# NetworkArduino.net
KiCad netlist of a schematic drawn in EAGLE
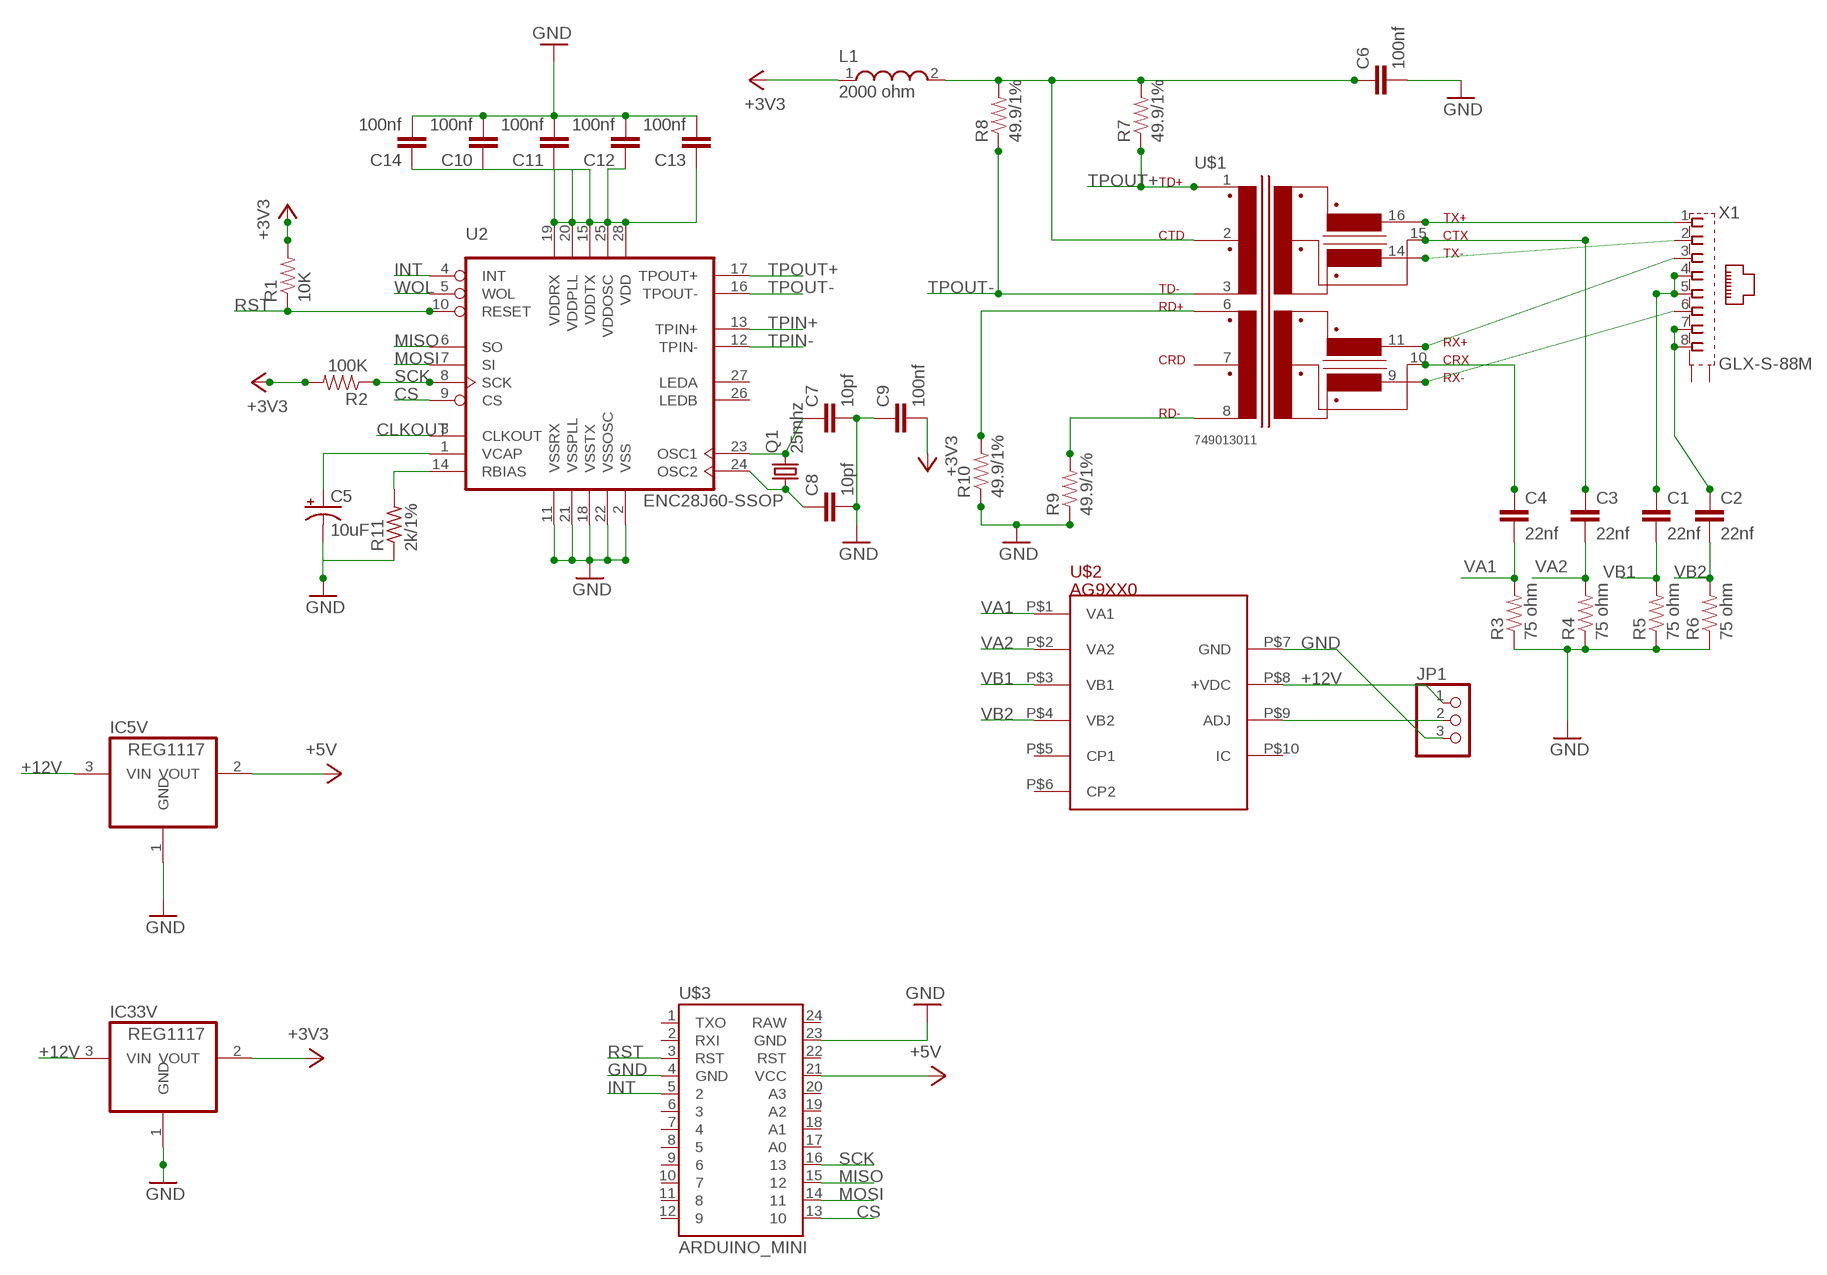
[diagram p0: schematic, sheet 1]

(export (version "E")
  (design (tool "Eeschema 10.0.6"))
  (components
    (comp (ref "C1")
      (value "22nf")
      (footprint "eagle-import:0805")
      (libsource (lib "eagle-import") (part "CAP0805"))
    )
    (comp (ref "C2")
      (value "22nf")
      (footprint "eagle-import:0805")
      (libsource (lib "eagle-import") (part "CAP0805"))
    )
    (comp (ref "C3")
      (value "22nf")
      (footprint "eagle-import:0805")
      (libsource (lib "eagle-import") (part "CAP0805"))
    )
    (comp (ref "C4")
      (value "22nf")
      (footprint "eagle-import:0805")
      (libsource (lib "eagle-import") (part "CAP0805"))
    )
    (comp (ref "C5")
      (value "10uF")
      (footprint "eagle-import:EIA3216")
      (libsource (lib "eagle-import") (part "10UF-16V-10%(TANT)"))
    )
    (comp (ref "C6")
      (value "100nf")
      (footprint "eagle-import:0805")
      (libsource (lib "eagle-import") (part "CAP0805"))
    )
    (comp (ref "C7")
      (value "10pf")
      (footprint "eagle-import:0805")
      (libsource (lib "eagle-import") (part "CAP0805"))
    )
    (comp (ref "C8")
      (value "10pf")
      (footprint "eagle-import:0805")
      (libsource (lib "eagle-import") (part "CAP0805"))
    )
    (comp (ref "C9")
      (value "100nf")
      (footprint "eagle-import:0805")
      (libsource (lib "eagle-import") (part "CAP0805"))
    )
    (comp (ref "C10")
      (value "100nf")
      (footprint "eagle-import:0805")
      (libsource (lib "eagle-import") (part "CAP0805"))
    )
    (comp (ref "C11")
      (value "100nf")
      (footprint "eagle-import:0805")
      (libsource (lib "eagle-import") (part "CAP0805"))
    )
    (comp (ref "C12")
      (value "100nf")
      (footprint "eagle-import:0805")
      (libsource (lib "eagle-import") (part "CAP0805"))
    )
    (comp (ref "C13")
      (value "100nf")
      (footprint "eagle-import:0805")
      (libsource (lib "eagle-import") (part "CAP0805"))
    )
    (comp (ref "C14")
      (value "100nf")
      (footprint "eagle-import:0805")
      (libsource (lib "eagle-import") (part "CAP0805"))
    )
    (comp (ref "IC5V")
      (value "REG1117")
      (footprint "eagle-import:SOT223")
      (libsource (lib "eagle-import") (part "REG1117"))
    )
    (comp (ref "IC33V")
      (value "REG1117")
      (footprint "eagle-import:SOT223")
      (libsource (lib "eagle-import") (part "REG1117"))
    )
    (comp (ref "JP1")
      (value "PINHD-1X3")
      (footprint "eagle-import:1X03")
      (libsource (lib "eagle-import") (part "PINHD-1X3"))
    )
    (comp (ref "L1")
      (value "2000 ohm")
      (footprint "eagle-import:WE-CBA_0805(W=3)")
      (libsource (lib "eagle-import") (part "WE-CBA_0805(WB/HS)"))
    )
    (comp (ref "Q1")
      (value "25mhz")
      (footprint "eagle-import:HC49UP")
      (libsource (lib "eagle-import") (part "CRYSTALHC49UP"))
    )
    (comp (ref "R1")
      (value "10K")
      (footprint "eagle-import:0805")
      (libsource (lib "eagle-import") (part "RESISTOR0805-RES"))
    )
    (comp (ref "R2")
      (value "100K")
      (footprint "eagle-import:0805")
      (libsource (lib "eagle-import") (part "RESISTOR0805-RES"))
    )
    (comp (ref "R3")
      (value "75 ohm")
      (footprint "eagle-import:0805")
      (libsource (lib "eagle-import") (part "RESISTOR0805-RES"))
    )
    (comp (ref "R4")
      (value "75 ohm")
      (footprint "eagle-import:0805")
      (libsource (lib "eagle-import") (part "RESISTOR0805-RES"))
    )
    (comp (ref "R5")
      (value "75 ohm")
      (footprint "eagle-import:0805")
      (libsource (lib "eagle-import") (part "RESISTOR0805-RES"))
    )
    (comp (ref "R6")
      (value "75 ohm")
      (footprint "eagle-import:0805")
      (libsource (lib "eagle-import") (part "RESISTOR0805-RES"))
    )
    (comp (ref "R7")
      (value "49.9/1%")
      (footprint "eagle-import:0805")
      (libsource (lib "eagle-import") (part "RESISTOR0805-RES"))
    )
    (comp (ref "R8")
      (value "49.9/1%")
      (footprint "eagle-import:0805")
      (libsource (lib "eagle-import") (part "RESISTOR0805-RES"))
    )
    (comp (ref "R9")
      (value "49.9/1%")
      (footprint "eagle-import:0805")
      (libsource (lib "eagle-import") (part "RESISTOR0805-RES"))
    )
    (comp (ref "R10")
      (value "49.9/1%")
      (footprint "eagle-import:0805")
      (libsource (lib "eagle-import") (part "RESISTOR0805-RES"))
    )
    (comp (ref "R11")
      (value "2k/1%")
      (footprint "eagle-import:R0805")
      (libsource (lib "eagle-import") (part "R-US_R0805"))
    )
    (comp (ref "U$1")
      (value "749013011")
      (footprint "eagle-import:749013011")
      (libsource (lib "eagle-import") (part "749013011"))
    )
    (comp (ref "U$2")
      (value "AG9XX0")
      (footprint "eagle-import:AG9000")
      (libsource (lib "eagle-import") (part "AG9XX0"))
    )
    (comp (ref "U$3")
      (value "ARDUINO_MINI")
      (footprint "eagle-import:ARDUINO_MINI")
      (libsource (lib "eagle-import") (part "ARDUINO_MINI"))
    )
    (comp (ref "U2")
      (value "ENC28J60-SSOP")
      (footprint "eagle-import:SSOP28")
      (libsource (lib "eagle-import") (part "ENC28J60-SSOP"))
    )
    (comp (ref "X1")
      (value "GLX-S-88M")
      (footprint "eagle-import:GLX-S-88M")
      (libsource (lib "eagle-import") (part "GLX-S-88M"))
    )
  )
  (nets
    (net (code "1") (name "+3V3") (class "Default")
      (node (ref "C9") (pin "2") (pinfunction "2_2") (pintype "passive"))
      (node (ref "IC33V") (pin "2") (pinfunction "VOUT_2") (pintype "output"))
      (node (ref "L1") (pin "1") (pinfunction "1_1") (pintype "passive"))
      (node (ref "R1") (pin "2") (pinfunction "2_2") (pintype "passive"))
      (node (ref "R2") (pin "2") (pinfunction "2_2") (pintype "passive"))
    )
    (net (code "2") (name "+5V") (class "Default")
      (node (ref "IC5V") (pin "2") (pinfunction "VOUT_2") (pintype "output"))
      (node (ref "U$3") (pin "21") (pinfunction "VCC_21") (pintype "bidirectional"))
    )
    (net (code "3") (name "/+12V") (class "Default")
      (node (ref "IC33V") (pin "3") (pinfunction "VIN_3") (pintype "input"))
      (node (ref "IC5V") (pin "3") (pinfunction "VIN_3") (pintype "input"))
      (node (ref "JP1") (pin "1") (pinfunction "1_1") (pintype "passive"))
      (node (ref "U$2") (pin "P$8") (pinfunction "+VDC_P$8") (pintype "power_in"))
    )
    (net (code "4") (name "/CLKOUT") (class "Default")
      (node (ref "U2") (pin "3") (pinfunction "CLKOUT_3") (pintype "output"))
    )
    (net (code "5") (name "/CS") (class "Default")
      (node (ref "U$3") (pin "13") (pinfunction "10_13") (pintype "bidirectional"))
      (node (ref "U2") (pin "9") (pinfunction "CS_9") (pintype "input"))
    )
    (net (code "6") (name "/INT") (class "Default")
      (node (ref "U$3") (pin "5") (pinfunction "2_5") (pintype "bidirectional"))
      (node (ref "U2") (pin "4") (pinfunction "INT_4") (pintype "output"))
    )
    (net (code "7") (name "/MISO") (class "Default")
      (node (ref "U$3") (pin "15") (pinfunction "12_15") (pintype "bidirectional"))
      (node (ref "U2") (pin "6") (pinfunction "SO_6") (pintype "output"))
    )
    (net (code "8") (name "/MOSI") (class "Default")
      (node (ref "U$3") (pin "14") (pinfunction "11_14") (pintype "bidirectional"))
      (node (ref "U2") (pin "7") (pinfunction "SI_7") (pintype "input"))
    )
    (net (code "9") (name "/RST") (class "Default")
      (node (ref "R1") (pin "1") (pinfunction "1_1") (pintype "passive"))
      (node (ref "U$3") (pin "3") (pinfunction "RST_3") (pintype "bidirectional"))
      (node (ref "U2") (pin "10") (pinfunction "RESET_10") (pintype "input"))
    )
    (net (code "10") (name "/SCK") (class "Default")
      (node (ref "R2") (pin "1") (pinfunction "1_1") (pintype "passive"))
      (node (ref "U$3") (pin "16") (pinfunction "13_16") (pintype "bidirectional"))
      (node (ref "U2") (pin "8") (pinfunction "SCK_8") (pintype "input"))
    )
    (net (code "11") (name "/TPIN+") (class "Default")
      (node (ref "R10") (pin "2") (pinfunction "2_2") (pintype "passive"))
      (node (ref "U$1") (pin "6") (pinfunction "4_6") (pintype "passive"))
      (node (ref "U2") (pin "13") (pinfunction "TPIN+_13") (pintype "input"))
    )
    (net (code "12") (name "/TPIN-") (class "Default")
      (node (ref "R9") (pin "2") (pinfunction "2_2") (pintype "passive"))
      (node (ref "U$1") (pin "8") (pinfunction "6_8") (pintype "passive"))
      (node (ref "U2") (pin "12") (pinfunction "TPIN-_12") (pintype "input"))
    )
    (net (code "13") (name "/TPOUT+") (class "Default")
      (node (ref "R7") (pin "1") (pinfunction "1_1") (pintype "passive"))
      (node (ref "U$1") (pin "1") (pinfunction "1_1") (pintype "passive"))
      (node (ref "U2") (pin "17") (pinfunction "TPOUT+_17") (pintype "output"))
    )
    (net (code "14") (name "/TPOUT-") (class "Default")
      (node (ref "R8") (pin "1") (pinfunction "1_1") (pintype "passive"))
      (node (ref "U$1") (pin "3") (pinfunction "3_3") (pintype "passive"))
      (node (ref "U2") (pin "16") (pinfunction "TPOUT-_16") (pintype "output"))
    )
    (net (code "15") (name "/VA1") (class "Default")
      (node (ref "C4") (pin "2") (pinfunction "2_2") (pintype "passive"))
      (node (ref "R3") (pin "2") (pinfunction "2_2") (pintype "passive"))
      (node (ref "U$2") (pin "P$1") (pinfunction "VA1_P$1") (pintype "input"))
    )
    (net (code "16") (name "/VA2") (class "Default")
      (node (ref "C3") (pin "2") (pinfunction "2_2") (pintype "passive"))
      (node (ref "R4") (pin "2") (pinfunction "2_2") (pintype "passive"))
      (node (ref "U$2") (pin "P$2") (pinfunction "VA2_P$2") (pintype "input"))
    )
    (net (code "17") (name "/VB1") (class "Default")
      (node (ref "C1") (pin "2") (pinfunction "2_2") (pintype "passive"))
      (node (ref "R5") (pin "2") (pinfunction "2_2") (pintype "passive"))
      (node (ref "U$2") (pin "P$3") (pinfunction "VB1_P$3") (pintype "input"))
    )
    (net (code "18") (name "/VB2") (class "Default")
      (node (ref "C2") (pin "2") (pinfunction "2_2") (pintype "passive"))
      (node (ref "R6") (pin "2") (pinfunction "2_2") (pintype "passive"))
      (node (ref "U$2") (pin "P$4") (pinfunction "VB2_P$4") (pintype "input"))
    )
    (net (code "19") (name "/WOL") (class "Default")
      (node (ref "U2") (pin "5") (pinfunction "WOL_5") (pintype "output"))
    )
    (net (code "20") (name "GND") (class "Default")
      (node (ref "C10") (pin "2") (pinfunction "2_2") (pintype "passive"))
      (node (ref "C11") (pin "2") (pinfunction "2_2") (pintype "passive"))
      (node (ref "C12") (pin "2") (pinfunction "2_2") (pintype "passive"))
      (node (ref "C13") (pin "2") (pinfunction "2_2") (pintype "passive"))
      (node (ref "C14") (pin "2") (pinfunction "2_2") (pintype "passive"))
      (node (ref "C5") (pin "C") (pinfunction "-_C") (pintype "passive"))
      (node (ref "C6") (pin "2") (pinfunction "2_2") (pintype "passive"))
      (node (ref "C7") (pin "2") (pinfunction "2_2") (pintype "passive"))
      (node (ref "C8") (pin "2") (pinfunction "2_2") (pintype "passive"))
      (node (ref "C9") (pin "1") (pinfunction "1_1") (pintype "passive"))
      (node (ref "IC33V") (pin "1") (pinfunction "GND_1") (pintype "power_in"))
      (node (ref "IC5V") (pin "1") (pinfunction "GND_1") (pintype "power_in"))
      (node (ref "JP1") (pin "3") (pinfunction "3_3") (pintype "passive"))
      (node (ref "R10") (pin "1") (pinfunction "1_1") (pintype "passive"))
      (node (ref "R11") (pin "1") (pinfunction "1_1") (pintype "passive"))
      (node (ref "R3") (pin "1") (pinfunction "1_1") (pintype "passive"))
      (node (ref "R4") (pin "1") (pinfunction "1_1") (pintype "passive"))
      (node (ref "R5") (pin "1") (pinfunction "1_1") (pintype "passive"))
      (node (ref "R6") (pin "1") (pinfunction "1_1") (pintype "passive"))
      (node (ref "R9") (pin "1") (pinfunction "1_1") (pintype "passive"))
      (node (ref "U$2") (pin "P$7") (pinfunction "GND_P$7") (pintype "power_in"))
      (node (ref "U$3") (pin "23") (pinfunction "GND_23") (pintype "bidirectional"))
      (node (ref "U$3") (pin "4") (pinfunction "GND_4") (pintype "bidirectional"))
      (node (ref "U2") (pin "11") (pinfunction "VSSRX_11") (pintype "power_in"))
      (node (ref "U2") (pin "18") (pinfunction "VSSTX_18") (pintype "power_in"))
      (node (ref "U2") (pin "2") (pinfunction "VSS_2") (pintype "power_in"))
      (node (ref "U2") (pin "21") (pinfunction "VSSPLL_21") (pintype "power_in"))
      (node (ref "U2") (pin "22") (pinfunction "VSSOSC_22") (pintype "power_in"))
    )
    (net (code "21") (name "Net-(C1-Pad1)") (class "Default")
      (node (ref "C1") (pin "1") (pinfunction "1_1") (pintype "passive"))
      (node (ref "X1") (pin "4") (pinfunction "4_4") (pintype "passive"))
      (node (ref "X1") (pin "5") (pinfunction "5_5") (pintype "passive"))
    )
    (net (code "22") (name "Net-(C2-Pad1)") (class "Default")
      (node (ref "C2") (pin "1") (pinfunction "1_1") (pintype "passive"))
      (node (ref "X1") (pin "7") (pinfunction "7_7") (pintype "passive"))
      (node (ref "X1") (pin "8") (pinfunction "8_8") (pintype "passive"))
    )
    (net (code "23") (name "Net-(C5-+)") (class "Default")
      (node (ref "C5") (pin "A") (pinfunction "+_A") (pintype "passive"))
      (node (ref "U2") (pin "1") (pinfunction "VCAP_1") (pintype "power_in"))
    )
    (net (code "24") (name "Net-(C6-Pad1)") (class "Default")
      (node (ref "C6") (pin "1") (pinfunction "1_1") (pintype "passive"))
      (node (ref "L1") (pin "2") (pinfunction "2_2") (pintype "passive"))
      (node (ref "R7") (pin "2") (pinfunction "2_2") (pintype "passive"))
      (node (ref "R8") (pin "2") (pinfunction "2_2") (pintype "passive"))
      (node (ref "U$1") (pin "2") (pinfunction "2_2") (pintype "passive"))
    )
    (net (code "25") (name "Net-(U$1-7)") (class "Default")
      (node (ref "U$1") (pin "16") (pinfunction "7_16") (pintype "passive"))
      (node (ref "X1") (pin "1") (pinfunction "1_1") (pintype "passive"))
    )
    (net (code "26") (name "Net-(U$1-8)") (class "Default")
      (node (ref "C3") (pin "1") (pinfunction "1_1") (pintype "passive"))
      (node (ref "U$1") (pin "15") (pinfunction "8_15") (pintype "passive"))
    )
    (net (code "27") (name "Net-(U$1-9)") (class "Default")
      (node (ref "U$1") (pin "14") (pinfunction "9_14") (pintype "passive"))
      (node (ref "X1") (pin "2") (pinfunction "2_2") (pintype "passive"))
    )
    (net (code "28") (name "Net-(U$1-10)") (class "Default")
      (node (ref "U$1") (pin "11") (pinfunction "10_11") (pintype "passive"))
      (node (ref "X1") (pin "3") (pinfunction "3_3") (pintype "passive"))
    )
    (net (code "29") (name "Net-(U$1-11)") (class "Default")
      (node (ref "C4") (pin "1") (pinfunction "1_1") (pintype "passive"))
      (node (ref "U$1") (pin "10") (pinfunction "11_10") (pintype "passive"))
    )
    (net (code "30") (name "Net-(U$1-12)") (class "Default")
      (node (ref "U$1") (pin "9") (pinfunction "12_9") (pintype "passive"))
      (node (ref "X1") (pin "6") (pinfunction "6_6") (pintype "passive"))
    )
    (net (code "31") (name "Net-(U$2-ADJ)") (class "Default")
      (node (ref "JP1") (pin "2") (pinfunction "2_2") (pintype "passive"))
      (node (ref "U$2") (pin "P$9") (pinfunction "ADJ_P$9") (pintype "passive"))
    )
    (net (code "32") (name "Net-(U2-OSC1)") (class "Default")
      (node (ref "C7") (pin "1") (pinfunction "1_1") (pintype "passive"))
      (node (ref "Q1") (pin "2") (pinfunction "2_2") (pintype "passive"))
      (node (ref "U2") (pin "23") (pinfunction "OSC1_23") (pintype "input"))
    )
    (net (code "33") (name "Net-(U2-OSC2)") (class "Default")
      (node (ref "C8") (pin "1") (pinfunction "1_1") (pintype "passive"))
      (node (ref "Q1") (pin "1") (pinfunction "1_1") (pintype "passive"))
      (node (ref "U2") (pin "24") (pinfunction "OSC2_24") (pintype "output"))
    )
    (net (code "34") (name "Net-(U2-RBIAS)") (class "Default")
      (node (ref "R11") (pin "2") (pinfunction "2_2") (pintype "passive"))
      (node (ref "U2") (pin "14") (pinfunction "RBIAS_14") (pintype "passive"))
    )
    (net (code "35") (name "Net-(U2-VDD)") (class "Default")
      (node (ref "C10") (pin "1") (pinfunction "1_1") (pintype "passive"))
      (node (ref "C11") (pin "1") (pinfunction "1_1") (pintype "passive"))
      (node (ref "C12") (pin "1") (pinfunction "1_1") (pintype "passive"))
      (node (ref "C13") (pin "1") (pinfunction "1_1") (pintype "passive"))
      (node (ref "C14") (pin "1") (pinfunction "1_1") (pintype "passive"))
      (node (ref "U2") (pin "15") (pinfunction "VDDTX_15") (pintype "power_in"))
      (node (ref "U2") (pin "19") (pinfunction "VDDRX_19") (pintype "power_in"))
      (node (ref "U2") (pin "20") (pinfunction "VDDPLL_20") (pintype "power_in"))
      (node (ref "U2") (pin "25") (pinfunction "VDDOSC_25") (pintype "power_in"))
      (node (ref "U2") (pin "28") (pinfunction "VDD_28") (pintype "power_in"))
    )
    (net (code "36") (name "unconnected-(U$1-5-Pad7)") (class "Default")
      (node (ref "U$1") (pin "7") (pinfunction "5_7") (pintype "passive"))
    )
    (net (code "37") (name "unconnected-(U$2-CP1-PadP$5)") (class "Default")
      (node (ref "U$2") (pin "P$5") (pinfunction "CP1_P$5") (pintype "input"))
    )
    (net (code "38") (name "unconnected-(U$2-CP2-PadP$6)") (class "Default")
      (node (ref "U$2") (pin "P$6") (pinfunction "CP2_P$6") (pintype "input"))
    )
    (net (code "39") (name "unconnected-(U$2-IC-PadP$10)") (class "Default")
      (node (ref "U$2") (pin "P$10") (pinfunction "IC_P$10") (pintype "no_connect"))
    )
    (net (code "40") (name "unconnected-(U$3-3-Pad6)") (class "Default")
      (node (ref "U$3") (pin "6") (pinfunction "3_6") (pintype "bidirectional"))
    )
    (net (code "41") (name "unconnected-(U$3-4-Pad7)") (class "Default")
      (node (ref "U$3") (pin "7") (pinfunction "4_7") (pintype "bidirectional"))
    )
    (net (code "42") (name "unconnected-(U$3-5-Pad8)") (class "Default")
      (node (ref "U$3") (pin "8") (pinfunction "5_8") (pintype "bidirectional"))
    )
    (net (code "43") (name "unconnected-(U$3-6-Pad9)") (class "Default")
      (node (ref "U$3") (pin "9") (pinfunction "6_9") (pintype "bidirectional"))
    )
    (net (code "44") (name "unconnected-(U$3-7-Pad10)") (class "Default")
      (node (ref "U$3") (pin "10") (pinfunction "7_10") (pintype "bidirectional"))
    )
    (net (code "45") (name "unconnected-(U$3-8-Pad11)") (class "Default")
      (node (ref "U$3") (pin "11") (pinfunction "8_11") (pintype "bidirectional"))
    )
    (net (code "46") (name "unconnected-(U$3-9-Pad12)") (class "Default")
      (node (ref "U$3") (pin "12") (pinfunction "9_12") (pintype "bidirectional"))
    )
    (net (code "47") (name "unconnected-(U$3-A0-Pad17)") (class "Default")
      (node (ref "U$3") (pin "17") (pinfunction "A0_17") (pintype "bidirectional"))
    )
    (net (code "48") (name "unconnected-(U$3-A1-Pad18)") (class "Default")
      (node (ref "U$3") (pin "18") (pinfunction "A1_18") (pintype "bidirectional"))
    )
    (net (code "49") (name "unconnected-(U$3-A2-Pad19)") (class "Default")
      (node (ref "U$3") (pin "19") (pinfunction "A2_19") (pintype "bidirectional"))
    )
    (net (code "50") (name "unconnected-(U$3-A3-Pad20)") (class "Default")
      (node (ref "U$3") (pin "20") (pinfunction "A3_20") (pintype "bidirectional"))
    )
    (net (code "51") (name "unconnected-(U$3-RAW-Pad24)") (class "Default")
      (node (ref "U$3") (pin "24") (pinfunction "RAW_24") (pintype "bidirectional"))
    )
    (net (code "52") (name "unconnected-(U$3-RST-Pad22)") (class "Default")
      (node (ref "U$3") (pin "22") (pinfunction "RST_22") (pintype "bidirectional"))
    )
    (net (code "53") (name "unconnected-(U$3-RXI-Pad2)") (class "Default")
      (node (ref "U$3") (pin "2") (pinfunction "RXI_2") (pintype "bidirectional"))
    )
    (net (code "54") (name "unconnected-(U$3-TXO-Pad1)") (class "Default")
      (node (ref "U$3") (pin "1") (pinfunction "TXO_1") (pintype "bidirectional"))
    )
    (net (code "55") (name "unconnected-(U2-LEDA-Pad27)") (class "Default")
      (node (ref "U2") (pin "27") (pinfunction "LEDA_27") (pintype "output"))
    )
    (net (code "56") (name "unconnected-(U2-LEDB-Pad26)") (class "Default")
      (node (ref "U2") (pin "26") (pinfunction "LEDB_26") (pintype "output"))
    )
    (net (code "57") (name "unconnected-(X1-PadS1)") (class "Default")
      (node (ref "X1") (pin "S1") (pinfunction "S1_S1") (pintype "passive"))
    )
    (net (code "58") (name "unconnected-(X1-PadS2)") (class "Default")
      (node (ref "X1") (pin "S2") (pinfunction "S2_S2") (pintype "passive"))
    )
  )
)
